# S04.net
KiCad netlist of a schematic drawn in Altium Designer
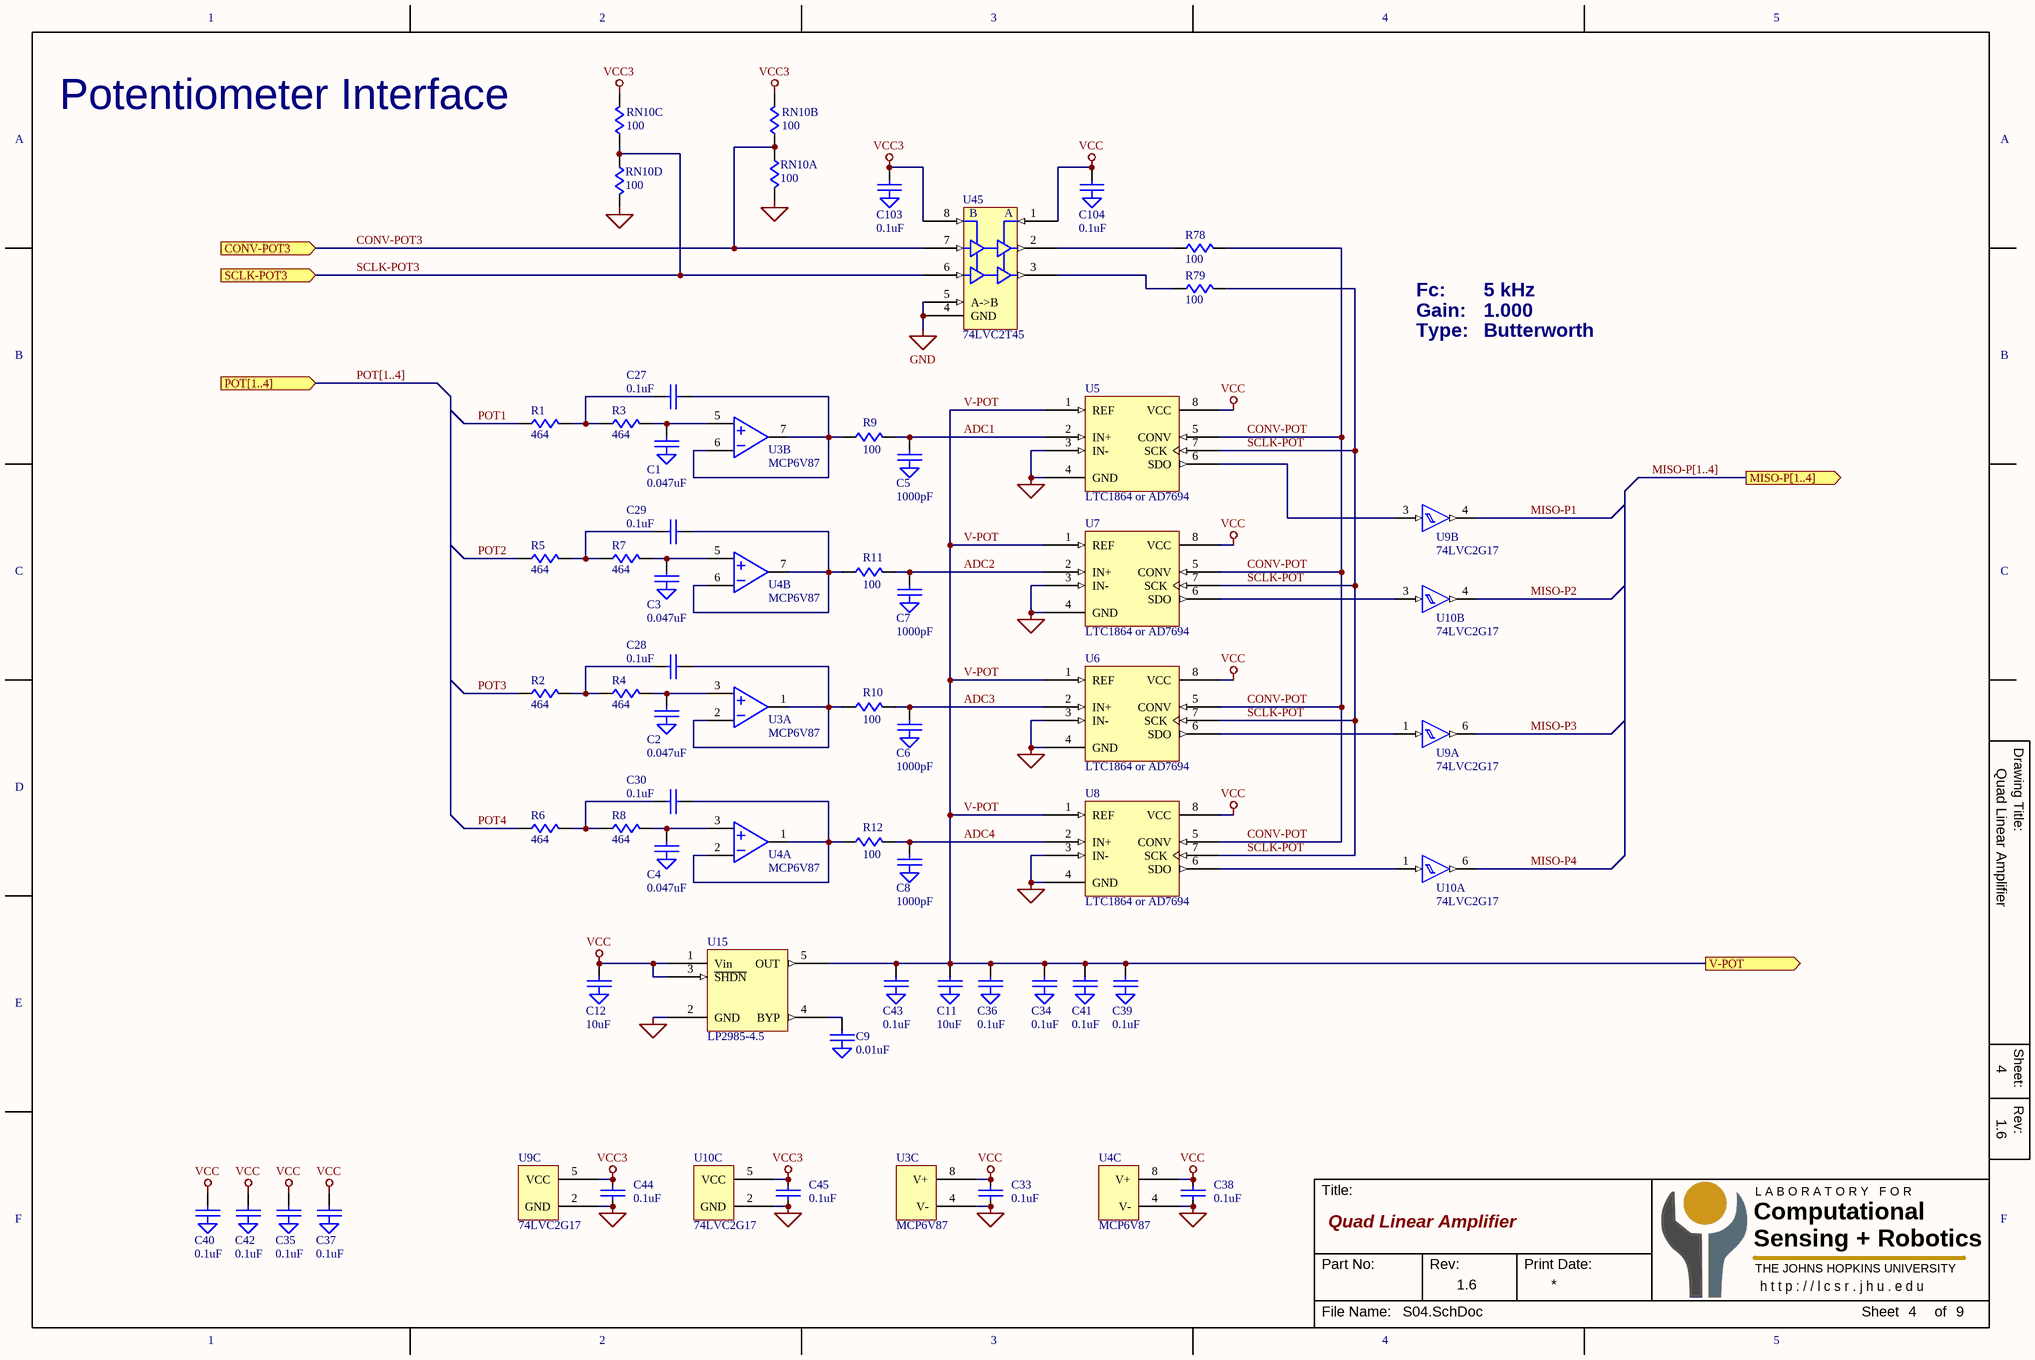
[diagram p0: S04.SchDoc]

(export (version "E")
  (design (tool "Eeschema 10.0.6"))
  (components
    (comp (ref "C1") (value "0.047uF") (footprint "C0603") (libsource (lib "QLA") (part "CAP-GND")))
    (comp (ref "C2") (value "0.047uF") (footprint "C0603") (libsource (lib "QLA") (part "CAP-GND")))
    (comp (ref "C3") (value "0.047uF") (footprint "C0603") (libsource (lib "QLA") (part "CAP-GND")))
    (comp (ref "C4") (value "0.047uF") (footprint "C0603") (libsource (lib "QLA") (part "CAP-GND")))
    (comp (ref "C5") (value "1000pF") (footprint "C0603") (libsource (lib "QLA") (part "CAP-GND")))
    (comp (ref "C6") (value "1000pF") (footprint "C0603") (libsource (lib "QLA") (part "CAP-GND")))
    (comp (ref "C7") (value "1000pF") (footprint "C0603") (libsource (lib "QLA") (part "CAP-GND")))
    (comp (ref "C8") (value "1000pF") (footprint "C0603") (libsource (lib "QLA") (part "CAP-GND")))
    (comp (ref "C9") (value "0.01uF") (footprint "C0603") (libsource (lib "QLA") (part "CAP-GND")))
    (comp (ref "C11") (value "10uF") (footprint "C0603") (libsource (lib "QLA") (part "CAP-GND")))
    (comp (ref "C12") (value "10uF") (footprint "C0603") (libsource (lib "QLA") (part "CAP-GND")))
    (comp (ref "C27") (value "0.1uF") (footprint "C0603") (libsource (lib "QLA") (part "CAP")))
    (comp (ref "C28") (value "0.1uF") (footprint "C0603") (libsource (lib "QLA") (part "CAP")))
    (comp (ref "C29") (value "0.1uF") (footprint "C0603") (libsource (lib "QLA") (part "CAP")))
    (comp (ref "C30") (value "0.1uF") (footprint "C0603") (libsource (lib "QLA") (part "CAP")))
    (comp (ref "C33") (value "0.1uF") (footprint "C0603") (libsource (lib "QLA") (part "CAP-MINI")))
    (comp (ref "C34") (value "0.1uF") (footprint "C0603") (libsource (lib "QLA") (part "CAP-GND")))
    (comp (ref "C35") (value "0.1uF") (footprint "C0603") (libsource (lib "QLA") (part "CAP-GND")))
    (comp (ref "C36") (value "0.1uF") (footprint "C0603") (libsource (lib "QLA") (part "CAP-GND")))
    (comp (ref "C37") (value "0.1uF") (footprint "C0603") (libsource (lib "QLA") (part "CAP-GND")))
    (comp (ref "C38") (value "0.1uF") (footprint "C0603") (libsource (lib "QLA") (part "CAP-MINI")))
    (comp (ref "C39") (value "0.1uF") (footprint "C0603") (libsource (lib "QLA") (part "CAP-GND")))
    (comp (ref "C40") (value "0.1uF") (footprint "C0603") (libsource (lib "QLA") (part "CAP-GND")))
    (comp (ref "C41") (value "0.1uF") (footprint "C0603") (libsource (lib "QLA") (part "CAP-GND")))
    (comp (ref "C42") (value "0.1uF") (footprint "C0603") (libsource (lib "QLA") (part "CAP-GND")))
    (comp (ref "C43") (value "0.1uF") (footprint "C0603") (libsource (lib "QLA") (part "CAP-GND")))
    (comp (ref "C44") (value "0.1uF") (footprint "C0603") (libsource (lib "QLA") (part "CAP-MINI")))
    (comp (ref "C45") (value "0.1uF") (footprint "C0603") (libsource (lib "QLA") (part "CAP-MINI")))
    (comp (ref "C103") (value "0.1uF") (footprint "C0603") (libsource (lib "") (part "CAP-GND_1")))
    (comp (ref "C104") (value "0.1uF") (footprint "C0603") (libsource (lib "") (part "CAP-GND_1")))
    (comp (ref "R1") (value "464") (footprint "R0603") (libsource (lib "QLA") (part "R")))
    (comp (ref "R2") (value "464") (footprint "R0603") (libsource (lib "QLA") (part "R")))
    (comp (ref "R3") (value "464") (footprint "R0603") (libsource (lib "QLA") (part "R")))
    (comp (ref "R4") (value "464") (footprint "R0603") (libsource (lib "QLA") (part "R")))
    (comp (ref "R5") (value "464") (footprint "R0603") (libsource (lib "QLA") (part "R")))
    (comp (ref "R6") (value "464") (footprint "R0603") (libsource (lib "QLA") (part "R")))
    (comp (ref "R7") (value "464") (footprint "R0603") (libsource (lib "QLA") (part "R")))
    (comp (ref "R8") (value "464") (footprint "R0603") (libsource (lib "QLA") (part "R")))
    (comp (ref "R9") (value "100") (footprint "R0603") (libsource (lib "QLA") (part "R")))
    (comp (ref "R10") (value "100") (footprint "R0603") (libsource (lib "QLA") (part "R")))
    (comp (ref "R11") (value "100") (footprint "R0603") (libsource (lib "QLA") (part "R")))
    (comp (ref "R12") (value "100") (footprint "R0603") (libsource (lib "QLA") (part "R")))
    (comp (ref "R78") (value "100") (footprint "R0603") (libsource (lib "QLA") (part "R")))
    (comp (ref "R79") (value "100") (footprint "R0603") (libsource (lib "QLA") (part "R")))
    (comp (ref "RN10") (value "100") (footprint "RN-742C083") (libsource (lib "QLA") (part "RN-DISC-SM-4X")))
    (comp (ref "U3")
      (value "MCP6V87")
      (footprint "MSOP-8")
      (libsource (lib "QLA") (part "OPAMP-DUAL-PWR-MINI"))
    )
    (comp (ref "U4")
      (value "MCP6V87")
      (footprint "MSOP-8")
      (libsource (lib "QLA") (part "OPAMP-DUAL-PWR-MINI"))
    )
    (comp (ref "U5")
      (value "LTC1864 or AD7694")
      (footprint "MSOP-8")
      (libsource (lib "QLA") (part "LTC1864"))
    )
    (comp (ref "U6")
      (value "LTC1864 or AD7694")
      (footprint "MSOP-8")
      (libsource (lib "QLA") (part "LTC1864"))
    )
    (comp (ref "U7")
      (value "LTC1864 or AD7694")
      (footprint "MSOP-8")
      (libsource (lib "QLA") (part "LTC1864"))
    )
    (comp (ref "U8")
      (value "LTC1864 or AD7694")
      (footprint "MSOP-8")
      (libsource (lib "QLA") (part "LTC1864"))
    )
    (comp (ref "U9")
      (value "74LVC2G17")
      (footprint "SOT-23-6")
      (description "NC7WZ17")
      (libsource (lib "QLA") (part "2G17"))
    )
    (comp (ref "U10")
      (value "74LVC2G17")
      (footprint "SOT-23-6")
      (description "NC7WZ17")
      (libsource (lib "QLA") (part "2G17"))
    )
    (comp (ref "U15") (value "LP2985-4.5") (footprint "SOT-23-5") (libsource (lib "QLA") (part "LP2985")))
    (comp (ref "U45") (value "74LVC2T45") (footprint "US8-8") (libsource (lib "QLA") (part "74LVC2T45")))
  )
  (nets
    (net (code "1") (name "/ADC1") (class "Default")
      (node (ref "C5") (pin "1") (pintype "passive"))
      (node (ref "R9") (pin "2") (pinfunction "2_2") (pintype "passive"))
      (node (ref "U5") (pin "2") (pinfunction "IN+_2") (pintype "input"))
    )
    (net (code "2") (name "/ADC2") (class "Default")
      (node (ref "C7") (pin "1") (pintype "passive"))
      (node (ref "R11") (pin "2") (pinfunction "2_2") (pintype "passive"))
      (node (ref "U7") (pin "2") (pinfunction "IN+_2") (pintype "input"))
    )
    (net (code "3") (name "/ADC3") (class "Default")
      (node (ref "C6") (pin "1") (pintype "passive"))
      (node (ref "R10") (pin "2") (pinfunction "2_2") (pintype "passive"))
      (node (ref "U6") (pin "2") (pinfunction "IN+_2") (pintype "input"))
    )
    (net (code "4") (name "/ADC4") (class "Default")
      (node (ref "C8") (pin "1") (pintype "passive"))
      (node (ref "R12") (pin "2") (pinfunction "2_2") (pintype "passive"))
      (node (ref "U8") (pin "2") (pinfunction "IN+_2") (pintype "input"))
    )
    (net (code "5") (name "/CONV-POT") (class "Default")
      (node (ref "R78") (pin "2") (pinfunction "2_2") (pintype "passive"))
      (node (ref "U5") (pin "5") (pinfunction "CONV_5") (pintype "input"))
      (node (ref "U6") (pin "5") (pinfunction "CONV_5") (pintype "input"))
      (node (ref "U7") (pin "5") (pinfunction "CONV_5") (pintype "input"))
      (node (ref "U8") (pin "5") (pinfunction "CONV_5") (pintype "input"))
    )
    (net (code "6") (name "/CONV-POT3") (class "Default")
      (node (ref "RN10") (pin "1") (pinfunction "1_1") (pintype "passive"))
      (node (ref "RN10") (pin "2") (pinfunction "2_2") (pintype "passive"))
      (node (ref "U45") (pin "7") (pinfunction "B_7") (pintype "input"))
    )
    (net (code "7") (name "/MISO-P1") (class "Default") (node (ref "U9") (pin "4") (pintype "output")))
    (net (code "8") (name "/MISO-P2") (class "Default") (node (ref "U10") (pin "4") (pintype "output")))
    (net (code "9") (name "/MISO-P3") (class "Default") (node (ref "U9") (pin "6") (pintype "output")))
    (net (code "10") (name "/MISO-P4") (class "Default") (node (ref "U10") (pin "6") (pintype "output")))
    (net (code "12") (name "/POT1") (class "Default")
      (node (ref "R1") (pin "1") (pinfunction "1_1") (pintype "passive"))
    )
    (net (code "13") (name "/POT2") (class "Default")
      (node (ref "R5") (pin "1") (pinfunction "1_1") (pintype "passive"))
    )
    (net (code "14") (name "/POT3") (class "Default")
      (node (ref "R2") (pin "1") (pinfunction "1_1") (pintype "passive"))
    )
    (net (code "15") (name "/POT4") (class "Default")
      (node (ref "R6") (pin "1") (pinfunction "1_1") (pintype "passive"))
    )
    (net (code "17") (name "/SCLK-POT") (class "Default")
      (node (ref "R79") (pin "2") (pinfunction "2_2") (pintype "passive"))
      (node (ref "U5") (pin "7") (pinfunction "SCK_7") (pintype "input"))
      (node (ref "U6") (pin "7") (pinfunction "SCK_7") (pintype "input"))
      (node (ref "U7") (pin "7") (pinfunction "SCK_7") (pintype "input"))
      (node (ref "U8") (pin "7") (pinfunction "SCK_7") (pintype "input"))
    )
    (net (code "18") (name "/SCLK-POT3") (class "Default")
      (node (ref "RN10") (pin "3") (pinfunction "3_3") (pintype "passive"))
      (node (ref "RN10") (pin "4") (pinfunction "4_4") (pintype "passive"))
      (node (ref "U45") (pin "6") (pinfunction "B_6") (pintype "input"))
    )
    (net (code "19") (name "/V-POT") (class "Default")
      (node (ref "C11") (pin "1") (pintype "passive"))
      (node (ref "C34") (pin "1") (pintype "passive"))
      (node (ref "C36") (pin "1") (pintype "passive"))
      (node (ref "C39") (pin "1") (pintype "passive"))
      (node (ref "C41") (pin "1") (pintype "passive"))
      (node (ref "C43") (pin "1") (pintype "passive"))
      (node (ref "U15") (pin "5") (pinfunction "OUT_5") (pintype "output"))
      (node (ref "U5") (pin "1") (pinfunction "REF_1") (pintype "input"))
      (node (ref "U6") (pin "1") (pinfunction "REF_1") (pintype "input"))
      (node (ref "U7") (pin "1") (pinfunction "REF_1") (pintype "input"))
      (node (ref "U8") (pin "1") (pinfunction "REF_1") (pintype "input"))
    )
    (net (code "20") (name "GND") (class "Default")
      (node (ref "C1") (pin "2") (pinfunction "GND_2") (pintype "power_in"))
      (node (ref "C103") (pin "2") (pinfunction "GND_2") (pintype "power_in"))
      (node (ref "C104") (pin "2") (pinfunction "GND_2") (pintype "power_in"))
      (node (ref "C11") (pin "2") (pinfunction "GND_2") (pintype "power_in"))
      (node (ref "C12") (pin "2") (pinfunction "GND_2") (pintype "power_in"))
      (node (ref "C2") (pin "2") (pinfunction "GND_2") (pintype "power_in"))
      (node (ref "C3") (pin "2") (pinfunction "GND_2") (pintype "power_in"))
      (node (ref "C33") (pin "2") (pintype "passive"))
      (node (ref "C34") (pin "2") (pinfunction "GND_2") (pintype "power_in"))
      (node (ref "C35") (pin "2") (pinfunction "GND_2") (pintype "power_in"))
      (node (ref "C36") (pin "2") (pinfunction "GND_2") (pintype "power_in"))
      (node (ref "C37") (pin "2") (pinfunction "GND_2") (pintype "power_in"))
      (node (ref "C38") (pin "2") (pintype "passive"))
      (node (ref "C39") (pin "2") (pinfunction "GND_2") (pintype "power_in"))
      (node (ref "C4") (pin "2") (pinfunction "GND_2") (pintype "power_in"))
      (node (ref "C40") (pin "2") (pinfunction "GND_2") (pintype "power_in"))
      (node (ref "C41") (pin "2") (pinfunction "GND_2") (pintype "power_in"))
      (node (ref "C42") (pin "2") (pinfunction "GND_2") (pintype "power_in"))
      (node (ref "C43") (pin "2") (pinfunction "GND_2") (pintype "power_in"))
      (node (ref "C44") (pin "2") (pintype "passive"))
      (node (ref "C45") (pin "2") (pintype "passive"))
      (node (ref "C5") (pin "2") (pinfunction "GND_2") (pintype "power_in"))
      (node (ref "C6") (pin "2") (pinfunction "GND_2") (pintype "power_in"))
      (node (ref "C7") (pin "2") (pinfunction "GND_2") (pintype "power_in"))
      (node (ref "C8") (pin "2") (pinfunction "GND_2") (pintype "power_in"))
      (node (ref "C9") (pin "2") (pinfunction "GND_2") (pintype "power_in"))
      (node (ref "RN10") (pin "5") (pinfunction "5_5") (pintype "passive"))
      (node (ref "RN10") (pin "8") (pinfunction "8_8") (pintype "passive"))
      (node (ref "U10") (pin "2") (pinfunction "GND_2") (pintype "power_in"))
      (node (ref "U15") (pin "2") (pinfunction "GND_2") (pintype "power_in"))
      (node (ref "U3") (pin "4") (pinfunction "V-_4") (pintype "power_in"))
      (node (ref "U4") (pin "4") (pinfunction "V-_4") (pintype "power_in"))
      (node (ref "U45") (pin "4") (pinfunction "GND_4") (pintype "power_in"))
      (node (ref "U45") (pin "5") (pinfunction "A->B_5") (pintype "input"))
      (node (ref "U5") (pin "3") (pinfunction "IN-_3") (pintype "input"))
      (node (ref "U5") (pin "4") (pinfunction "GND_4") (pintype "power_in"))
      (node (ref "U6") (pin "3") (pinfunction "IN-_3") (pintype "input"))
      (node (ref "U6") (pin "4") (pinfunction "GND_4") (pintype "power_in"))
      (node (ref "U7") (pin "3") (pinfunction "IN-_3") (pintype "input"))
      (node (ref "U7") (pin "4") (pinfunction "GND_4") (pintype "power_in"))
      (node (ref "U8") (pin "3") (pinfunction "IN-_3") (pintype "input"))
      (node (ref "U8") (pin "4") (pinfunction "GND_4") (pintype "power_in"))
      (node (ref "U9") (pin "2") (pinfunction "GND_2") (pintype "power_in"))
    )
    (net (code "21") (name "Net-(C27-Pad1)") (class "Default")
      (node (ref "C27") (pin "1") (pintype "passive"))
      (node (ref "R1") (pin "2") (pinfunction "2_2") (pintype "passive"))
      (node (ref "R3") (pin "1") (pinfunction "1_1") (pintype "passive"))
    )
    (net (code "22") (name "Net-(C28-Pad1)") (class "Default")
      (node (ref "C28") (pin "1") (pintype "passive"))
      (node (ref "R2") (pin "2") (pinfunction "2_2") (pintype "passive"))
      (node (ref "R4") (pin "1") (pinfunction "1_1") (pintype "passive"))
    )
    (net (code "23") (name "Net-(C29-Pad1)") (class "Default")
      (node (ref "C29") (pin "1") (pintype "passive"))
      (node (ref "R5") (pin "2") (pinfunction "2_2") (pintype "passive"))
      (node (ref "R7") (pin "1") (pinfunction "1_1") (pintype "passive"))
    )
    (net (code "24") (name "Net-(C30-Pad1)") (class "Default")
      (node (ref "C30") (pin "1") (pintype "passive"))
      (node (ref "R6") (pin "2") (pinfunction "2_2") (pintype "passive"))
      (node (ref "R8") (pin "1") (pinfunction "1_1") (pintype "passive"))
    )
    (net (code "25") (name "Net-(R78-Pad1)") (class "Default")
      (node (ref "R78") (pin "1") (pinfunction "1_1") (pintype "passive"))
      (node (ref "U45") (pin "2") (pinfunction "A_2") (pintype "output"))
    )
    (net (code "26") (name "Net-(R79-Pad1)") (class "Default")
      (node (ref "R79") (pin "1") (pinfunction "1_1") (pintype "passive"))
      (node (ref "U45") (pin "3") (pinfunction "A_3") (pintype "output"))
    )
    (net (code "27") (name "Net-(U3A-IN+)") (class "Default")
      (node (ref "C2") (pin "1") (pintype "passive"))
      (node (ref "R4") (pin "2") (pinfunction "2_2") (pintype "passive"))
      (node (ref "U3") (pin "3") (pinfunction "IN+_3") (pintype "passive"))
    )
    (net (code "28") (name "Net-(U3A-IN-)") (class "Default")
      (node (ref "C28") (pin "2") (pintype "passive"))
      (node (ref "R10") (pin "1") (pinfunction "1_1") (pintype "passive"))
      (node (ref "U3") (pin "1") (pinfunction "O_1") (pintype "passive"))
      (node (ref "U3") (pin "2") (pinfunction "IN-_2") (pintype "passive"))
    )
    (net (code "29") (name "Net-(U3B-IN+)") (class "Default")
      (node (ref "C1") (pin "1") (pintype "passive"))
      (node (ref "R3") (pin "2") (pinfunction "2_2") (pintype "passive"))
      (node (ref "U3") (pin "5") (pinfunction "IN+_5") (pintype "passive"))
    )
    (net (code "30") (name "Net-(U3B-IN-)") (class "Default")
      (node (ref "C27") (pin "2") (pintype "passive"))
      (node (ref "R9") (pin "1") (pinfunction "1_1") (pintype "passive"))
      (node (ref "U3") (pin "6") (pinfunction "IN-_6") (pintype "passive"))
      (node (ref "U3") (pin "7") (pinfunction "O_7") (pintype "passive"))
    )
    (net (code "31") (name "Net-(U4A-IN+)") (class "Default")
      (node (ref "C4") (pin "1") (pintype "passive"))
      (node (ref "R8") (pin "2") (pinfunction "2_2") (pintype "passive"))
      (node (ref "U4") (pin "3") (pinfunction "IN+_3") (pintype "passive"))
    )
    (net (code "32") (name "Net-(U4A-IN-)") (class "Default")
      (node (ref "C30") (pin "2") (pintype "passive"))
      (node (ref "R12") (pin "1") (pinfunction "1_1") (pintype "passive"))
      (node (ref "U4") (pin "1") (pinfunction "O_1") (pintype "passive"))
      (node (ref "U4") (pin "2") (pinfunction "IN-_2") (pintype "passive"))
    )
    (net (code "33") (name "Net-(U4B-IN+)") (class "Default")
      (node (ref "C3") (pin "1") (pintype "passive"))
      (node (ref "R7") (pin "2") (pinfunction "2_2") (pintype "passive"))
      (node (ref "U4") (pin "5") (pinfunction "IN+_5") (pintype "passive"))
    )
    (net (code "34") (name "Net-(U4B-IN-)") (class "Default")
      (node (ref "C29") (pin "2") (pintype "passive"))
      (node (ref "R11") (pin "1") (pinfunction "1_1") (pintype "passive"))
      (node (ref "U4") (pin "6") (pinfunction "IN-_6") (pintype "passive"))
      (node (ref "U4") (pin "7") (pinfunction "O_7") (pintype "passive"))
    )
    (net (code "35") (name "Net-(U5-SDO)") (class "Default")
      (node (ref "U5") (pin "6") (pinfunction "SDO_6") (pintype "output"))
      (node (ref "U9") (pin "3") (pintype "input"))
    )
    (net (code "36") (name "Net-(U6-SDO)") (class "Default")
      (node (ref "U6") (pin "6") (pinfunction "SDO_6") (pintype "output"))
      (node (ref "U9") (pin "1") (pintype "input"))
    )
    (net (code "37") (name "Net-(U7-SDO)") (class "Default")
      (node (ref "U10") (pin "3") (pintype "input"))
      (node (ref "U7") (pin "6") (pinfunction "SDO_6") (pintype "output"))
    )
    (net (code "38") (name "Net-(U8-SDO)") (class "Default")
      (node (ref "U10") (pin "1") (pintype "input"))
      (node (ref "U8") (pin "6") (pinfunction "SDO_6") (pintype "output"))
    )
    (net (code "39") (name "Net-(U15-BYP)") (class "Default")
      (node (ref "C9") (pin "1") (pintype "passive"))
      (node (ref "U15") (pin "4") (pinfunction "BYP_4") (pintype "output"))
    )
    (net (code "40") (name "VCC") (class "Default")
      (node (ref "C104") (pin "1") (pintype "passive"))
      (node (ref "C12") (pin "1") (pintype "passive"))
      (node (ref "C33") (pin "1") (pintype "passive"))
      (node (ref "C35") (pin "1") (pintype "passive"))
      (node (ref "C37") (pin "1") (pintype "passive"))
      (node (ref "C38") (pin "1") (pintype "passive"))
      (node (ref "C40") (pin "1") (pintype "passive"))
      (node (ref "C42") (pin "1") (pintype "passive"))
      (node (ref "U15") (pin "1") (pinfunction "Vin_1") (pintype "power_in"))
      (node (ref "U15") (pin "3") (pinfunction "~{SHDN}_3") (pintype "input"))
      (node (ref "U3") (pin "8") (pinfunction "V+_8") (pintype "power_in"))
      (node (ref "U4") (pin "8") (pinfunction "V+_8") (pintype "power_in"))
      (node (ref "U45") (pin "1") (pinfunction "VCCA_1") (pintype "input"))
      (node (ref "U5") (pin "8") (pinfunction "VCC_8") (pintype "power_in"))
      (node (ref "U6") (pin "8") (pinfunction "VCC_8") (pintype "power_in"))
      (node (ref "U7") (pin "8") (pinfunction "VCC_8") (pintype "power_in"))
      (node (ref "U8") (pin "8") (pinfunction "VCC_8") (pintype "power_in"))
    )
    (net (code "41") (name "VCC3") (class "Default")
      (node (ref "C103") (pin "1") (pintype "passive"))
      (node (ref "C44") (pin "1") (pintype "passive"))
      (node (ref "C45") (pin "1") (pintype "passive"))
      (node (ref "RN10") (pin "6") (pinfunction "6_6") (pintype "passive"))
      (node (ref "RN10") (pin "7") (pinfunction "7_7") (pintype "passive"))
      (node (ref "U10") (pin "5") (pinfunction "VCC_5") (pintype "power_in"))
      (node (ref "U45") (pin "8") (pinfunction "VCCB_8") (pintype "input"))
      (node (ref "U9") (pin "5") (pinfunction "VCC_5") (pintype "power_in"))
    )
  )
)
